# Dash.net
KiCad netlist of a schematic drawn in Altium Designer
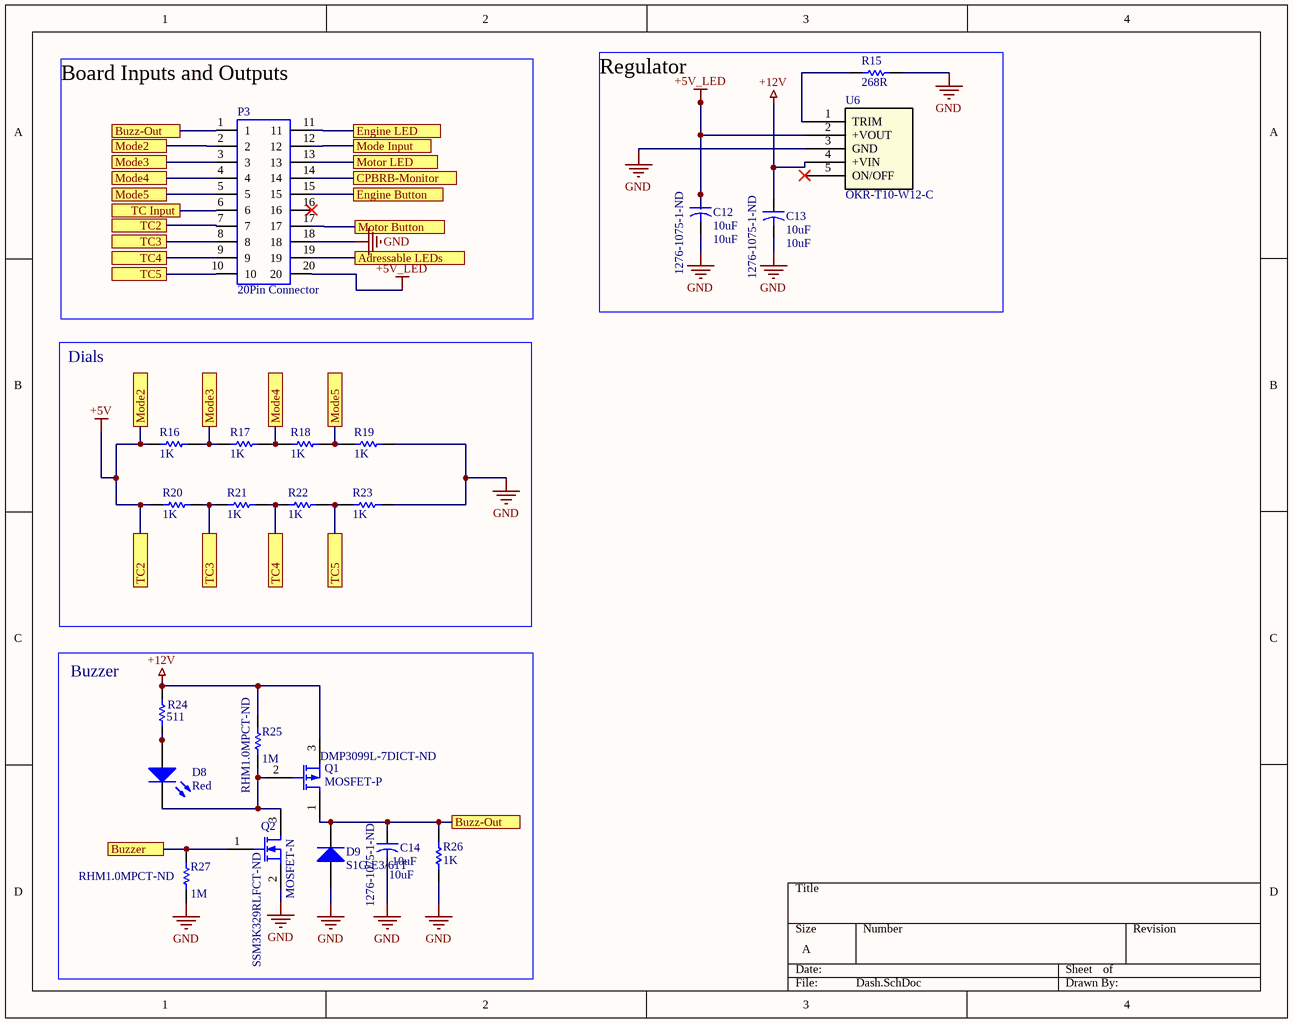
[diagram p0: Dash.SchDoc]

(export (version "E")
  (design (tool "Eeschema 10.0.6"))
  (components
    (comp (ref "C12")
      (value "10uF")
      (footprint "CAPC3216X170N")
      (description "Capacitor. Ceramic 10uF 50V rating recommended, place close to pin")
      (fields
        (field (name "ALTIUM_VALUE") "10uF")
        (field (name "SUPPLIER PART NUMBER") "1276-1075-1-ND")
        (field (name "PUBLISHER") "Altium Limited")
      )
      (libsource (lib "PowerDistLib") (part "Cap2"))
    )
    (comp (ref "C13")
      (value "10uF")
      (footprint "CAPC3216X170N")
      (description "Capacitor. Ceramic 10uF 50V rating recommended, place close to pin")
      (fields
        (field (name "ALTIUM_VALUE") "10uF")
        (field (name "SUPPLIER PART NUMBER") "1276-1075-1-ND")
        (field (name "PUBLISHER") "Altium Limited")
      )
      (libsource (lib "PowerDistLib") (part "Cap2"))
    )
    (comp (ref "C14")
      (value "10uF")
      (footprint "CAPC3216X170N")
      (description "Capacitor. Ceramic 10uF 50V rating recommended, place close to pin")
      (fields
        (field (name "ALTIUM_VALUE") "10uF")
        (field (name "SUPPLIER PART NUMBER") "1276-1075-1-ND")
        (field (name "PUBLISHER") "Altium Limited")
      )
      (libsource (lib "PowerDistLib") (part "Cap2"))
    )
    (comp (ref "D8")
      (value "Red")
      (footprint "LEDC3216X120NRED")
      (description "Typical RED, GREEN, YELLOW, AMBER GaAs LED")
      (fields
        (field (name "MANUFACTURER") "Broadcom Avago")
        (field (name "MANUFACTURER PART NUMBER") "HSMY-C150")
        (field (name "PUBLISHER") "Altium Limited")
      )
      (libsource (lib "Miscellaneous Devices") (part "LED2"))
    )
    (comp (ref "D9")
      (value "S1G-E3/61T")
      (footprint "VISH-DO-214AC-SMA-2_N")
      (fields (field (name "MANUFACTURER") "Vishay Semiconductor"))
      (libsource (lib "Integrated_Library1") (part "S1G-E3/61T"))
    )
    (comp (ref "P3")
      (value "20Pin Connector")
      (footprint "20Pin connector Molex")
      (description "Connector Header Through Hole 20 position 0.118\" (3.00mm) \r\n43045-2013")
      (fields (field (name "MANUFACTURER_PART_NUMBER") "43045-2013"))
      (libsource (lib "Connectors") (part "20Pin Connector"))
    )
    (comp (ref "Q1")
      (value "MOSFET-P")
      (footprint "SOT23-3")
      (description "P-Channel MOSFET")
      (fields
        (field (name "SUPPLIER PART NUMBER") "DMP3099L-7DICT-ND")
        (field (name "PUBLISHER") "Altium Limited")
      )
      (libsource (lib "Miscellaneous Devices") (part "MOSFET-P"))
    )
    (comp (ref "Q2")
      (value "MOSFET-N")
      (footprint "SOT23-3")
      (description "N-Channel MOSFET")
      (fields
        (field (name "SUPPLIER PART NUMBER") "SSM3K329RLFCT-ND")
        (field (name "PUBLISHER") "Altium Limited")
      )
      (libsource (lib "Miscellaneous Devices") (part "MOSFET-N"))
    )
    (comp (ref "R15")
      (value "268R")
      (footprint "RESC3216X60N")
      (description "Resistor")
      (fields
        (field (name "MANUFACTURER") "Stackpole Electronics")
        (field (name "MANUFACTURER PART NUMBER") "RMCF1206FT267R")
      )
      (libsource (lib "Candunio") (part "Res1"))
    )
    (comp (ref "R16")
      (value "1K")
      (footprint "RESC3216X60N")
      (description "Resistor")
      (fields
        (field (name "MANUFACTURER") "Stackpole Electronics")
        (field (name "MANUFACTURER PART NUMBER") "RNCP1206FTD1K00")
      )
      (libsource (lib "Miscellaneous Devices") (part "Res1"))
    )
    (comp (ref "R17")
      (value "1K")
      (footprint "RESC3216X60N")
      (description "Resistor")
      (fields
        (field (name "MANUFACTURER") "Stackpole Electronics")
        (field (name "MANUFACTURER PART NUMBER") "RNCP1206FTD1K00")
      )
      (libsource (lib "Miscellaneous Devices") (part "Res1"))
    )
    (comp (ref "R18")
      (value "1K")
      (footprint "RESC3216X60N")
      (description "Resistor")
      (fields
        (field (name "MANUFACTURER") "Stackpole Electronics")
        (field (name "MANUFACTURER PART NUMBER") "RNCP1206FTD1K00")
      )
      (libsource (lib "Miscellaneous Devices") (part "Res1"))
    )
    (comp (ref "R19")
      (value "1K")
      (footprint "RESC3216X60N")
      (description "Resistor")
      (fields
        (field (name "MANUFACTURER") "Stackpole Electronics")
        (field (name "MANUFACTURER PART NUMBER") "RNCP1206FTD1K00")
      )
      (libsource (lib "Miscellaneous Devices") (part "Res1"))
    )
    (comp (ref "R20")
      (value "1K")
      (footprint "RESC3216X60N")
      (description "Resistor")
      (fields
        (field (name "MANUFACTURER") "Stackpole Electronics")
        (field (name "MANUFACTURER PART NUMBER") "RNCP1206FTD1K00")
      )
      (libsource (lib "Miscellaneous Devices") (part "Res1"))
    )
    (comp (ref "R21")
      (value "1K")
      (footprint "RESC3216X60N")
      (description "Resistor")
      (fields
        (field (name "MANUFACTURER") "Stackpole Electronics")
        (field (name "MANUFACTURER PART NUMBER") "RNCP1206FTD1K00")
      )
      (libsource (lib "Miscellaneous Devices") (part "Res1"))
    )
    (comp (ref "R22")
      (value "1K")
      (footprint "RESC3216X60N")
      (description "Resistor")
      (fields
        (field (name "MANUFACTURER") "Stackpole Electronics")
        (field (name "MANUFACTURER PART NUMBER") "RNCP1206FTD1K00")
      )
      (libsource (lib "Miscellaneous Devices") (part "Res1"))
    )
    (comp (ref "R23")
      (value "1K")
      (footprint "RESC3216X60N")
      (description "Resistor")
      (fields
        (field (name "MANUFACTURER") "Stackpole Electronics")
        (field (name "MANUFACTURER PART NUMBER") "RNCP1206FTD1K00")
      )
      (libsource (lib "Miscellaneous Devices") (part "Res1"))
    )
    (comp (ref "R24")
      (value "511")
      (footprint "RESC3216X60N")
      (description "Resistor")
      (fields (field (name "PUBLISHER") "Altium Limited"))
      (libsource (lib "Miscellaneous Devices") (part "Res1"))
    )
    (comp (ref "R25")
      (value "1M")
      (footprint "RESC3216X60N")
      (description "Resistor")
      (fields
        (field (name "SUPPLIER PART NUMBER") "RHM1.0MPCT-ND")
        (field (name "Comment") "1206")
        (field (name "PUBLISHER") "Altium Limited")
      )
      (libsource (lib "Miscellaneous Devices") (part "Res1"))
    )
    (comp (ref "R26")
      (value "1K")
      (footprint "RESC3216X60N")
      (description "Resistor")
      (fields
        (field (name "MANUFACTURER") "Stackpole Electronics")
        (field (name "MANUFACTURER PART NUMBER") "RNCP1206FTD1K00")
      )
      (libsource (lib "Miscellaneous Devices") (part "Res1"))
    )
    (comp (ref "R27")
      (value "1M")
      (footprint "RESC3216X60N")
      (description "Resistor")
      (fields
        (field (name "SUPPLIER PART NUMBER") "RHM1.0MPCT-ND")
        (field (name "Comment") "1206")
        (field (name "PUBLISHER") "Altium Limited")
      )
      (libsource (lib "Miscellaneous Devices") (part "Res1"))
    )
    (comp (ref "U6")
      (value "OKR-T10-W12-C")
      (footprint "OKR-T10-W12-C")
      (description "DC DC CONVERTER 0.591-6V 50W")
      (fields (field (name "MANUFACTURER_PART_NUMBER") "OKR-T/10-W12-C"))
      (libsource (lib "SwitchingReg") (part "OKR-T10-W12-C"))
    )
  )
  (nets
    (net (code "1") (name "+5V") (class "Default")
      (node (ref "P3") (pin "2") (pinfunction "2_2") (pintype "passive"))
      (node (ref "P3") (pin "7") (pinfunction "7_7") (pintype "passive"))
      (node (ref "R16") (pin "1") (pinfunction "1_1") (pintype "passive"))
      (node (ref "R20") (pin "1") (pinfunction "1_1") (pintype "passive"))
    )
    (net (code "2") (name "+5V_LED") (class "Default")
      (node (ref "C12") (pin "1") (pinfunction "1_1") (pintype "passive"))
      (node (ref "P3") (pin "20") (pinfunction "20_20") (pintype "passive"))
      (node (ref "U6") (pin "2") (pinfunction "+VOUT_2") (pintype "power_in"))
    )
    (net (code "3") (name "+12V") (class "Default")
      (node (ref "C13") (pin "1") (pinfunction "1_1") (pintype "passive"))
      (node (ref "Q1") (pin "3") (pinfunction "S_3") (pintype "passive"))
      (node (ref "R24") (pin "1") (pinfunction "1_1") (pintype "passive"))
      (node (ref "R25") (pin "2") (pinfunction "2_2") (pintype "passive"))
      (node (ref "U6") (pin "4") (pinfunction "+VIN_4") (pintype "passive"))
    )
    (net (code "4") (name "/Adressable LEDs") (class "Default")
      (node (ref "P3") (pin "19") (pinfunction "19_19") (pintype "passive"))
    )
    (net (code "5") (name "/Buzz-Out") (class "Default")
      (node (ref "C14") (pin "1") (pinfunction "1_1") (pintype "passive"))
      (node (ref "D9") (pin "2") (pinfunction "K_2") (pintype "passive"))
      (node (ref "P3") (pin "1") (pinfunction "1_1") (pintype "passive"))
      (node (ref "Q1") (pin "1") (pinfunction "D_1") (pintype "passive"))
      (node (ref "R26") (pin "2") (pinfunction "2_2") (pintype "passive"))
    )
    (net (code "6") (name "/Buzzer") (class "Default")
      (node (ref "Q2") (pin "1") (pinfunction "G_1") (pintype "passive"))
      (node (ref "R27") (pin "2") (pinfunction "2_2") (pintype "passive"))
    )
    (net (code "7") (name "/CPBRB-Monitor") (class "Default")
      (node (ref "P3") (pin "14") (pinfunction "14_14") (pintype "passive"))
    )
    (net (code "8") (name "/Engine Button") (class "Default")
      (node (ref "P3") (pin "15") (pinfunction "15_15") (pintype "passive"))
    )
    (net (code "9") (name "/Engine LED") (class "Default")
      (node (ref "P3") (pin "11") (pinfunction "11_11") (pintype "passive"))
    )
    (net (code "10") (name "/Mode Input") (class "Default")
      (node (ref "P3") (pin "12") (pinfunction "12_12") (pintype "passive"))
    )
    (net (code "11") (name "/Mode3") (class "Default")
      (node (ref "P3") (pin "3") (pinfunction "3_3") (pintype "passive"))
      (node (ref "R16") (pin "2") (pinfunction "2_2") (pintype "passive"))
      (node (ref "R17") (pin "1") (pinfunction "1_1") (pintype "passive"))
    )
    (net (code "12") (name "/Mode4") (class "Default")
      (node (ref "P3") (pin "4") (pinfunction "4_4") (pintype "passive"))
      (node (ref "R17") (pin "2") (pinfunction "2_2") (pintype "passive"))
      (node (ref "R18") (pin "1") (pinfunction "1_1") (pintype "passive"))
    )
    (net (code "13") (name "/Mode5") (class "Default")
      (node (ref "P3") (pin "5") (pinfunction "5_5") (pintype "passive"))
      (node (ref "R18") (pin "2") (pinfunction "2_2") (pintype "passive"))
      (node (ref "R19") (pin "1") (pinfunction "1_1") (pintype "passive"))
    )
    (net (code "14") (name "/Motor Button") (class "Default")
      (node (ref "P3") (pin "17") (pinfunction "17_17") (pintype "passive"))
    )
    (net (code "15") (name "/Motor LED") (class "Default")
      (node (ref "P3") (pin "13") (pinfunction "13_13") (pintype "passive"))
    )
    (net (code "16") (name "/TC Input") (class "Default")
      (node (ref "P3") (pin "6") (pinfunction "6_6") (pintype "passive"))
    )
    (net (code "17") (name "/TC3") (class "Default")
      (node (ref "P3") (pin "8") (pinfunction "8_8") (pintype "passive"))
      (node (ref "R20") (pin "2") (pinfunction "2_2") (pintype "passive"))
      (node (ref "R21") (pin "1") (pinfunction "1_1") (pintype "passive"))
    )
    (net (code "18") (name "/TC4") (class "Default")
      (node (ref "P3") (pin "9") (pinfunction "9_9") (pintype "passive"))
      (node (ref "R21") (pin "2") (pinfunction "2_2") (pintype "passive"))
      (node (ref "R22") (pin "1") (pinfunction "1_1") (pintype "passive"))
    )
    (net (code "19") (name "/TC5") (class "Default")
      (node (ref "P3") (pin "10") (pinfunction "10_10") (pintype "passive"))
      (node (ref "R22") (pin "2") (pinfunction "2_2") (pintype "passive"))
      (node (ref "R23") (pin "1") (pinfunction "1_1") (pintype "passive"))
    )
    (net (code "20") (name "GND") (class "Default")
      (node (ref "C12") (pin "2") (pinfunction "2_2") (pintype "passive"))
      (node (ref "C13") (pin "2") (pinfunction "2_2") (pintype "passive"))
      (node (ref "C14") (pin "2") (pinfunction "2_2") (pintype "passive"))
      (node (ref "D9") (pin "1") (pinfunction "A_1") (pintype "passive"))
      (node (ref "P3") (pin "18") (pinfunction "18_18") (pintype "passive"))
      (node (ref "Q2") (pin "2") (pinfunction "S_2") (pintype "passive"))
      (node (ref "R15") (pin "1") (pinfunction "1_1") (pintype "passive"))
      (node (ref "R19") (pin "2") (pinfunction "2_2") (pintype "passive"))
      (node (ref "R23") (pin "2") (pinfunction "2_2") (pintype "passive"))
      (node (ref "R26") (pin "1") (pinfunction "1_1") (pintype "passive"))
      (node (ref "R27") (pin "1") (pinfunction "1_1") (pintype "passive"))
      (node (ref "U6") (pin "3") (pinfunction "GND_3") (pintype "passive"))
    )
    (net (code "21") (name "Net-(D8-A)") (class "Default")
      (node (ref "D8") (pin "1") (pinfunction "A_1") (pintype "passive"))
      (node (ref "R24") (pin "2") (pinfunction "2_2") (pintype "passive"))
    )
    (net (code "22") (name "Net-(D8-K)") (class "Default")
      (node (ref "D8") (pin "2") (pinfunction "K_2") (pintype "passive"))
      (node (ref "Q1") (pin "2") (pinfunction "G_2") (pintype "passive"))
      (node (ref "Q2") (pin "3") (pinfunction "D_3") (pintype "passive"))
      (node (ref "R25") (pin "1") (pinfunction "1_1") (pintype "passive"))
    )
    (net (code "23") (name "Net-(U6-TRIM)") (class "Default")
      (node (ref "R15") (pin "2") (pinfunction "2_2") (pintype "passive"))
      (node (ref "U6") (pin "1") (pinfunction "TRIM_1") (pintype "power_in"))
    )
    (net (code "24") (name "unconnected-(P3-Pad16)") (class "Default")
      (node (ref "P3") (pin "16") (pinfunction "16_16") (pintype "passive+no_connect"))
    )
    (net (code "25") (name "unconnected-(U6-ON{slash}OFF-Pad5)") (class "Default")
      (node (ref "U6") (pin "5") (pinfunction "ON/OFF_5") (pintype "passive+no_connect"))
    )
  )
)
